# MPU_9250.net
KiCad netlist of a schematic drawn in Altium Designer
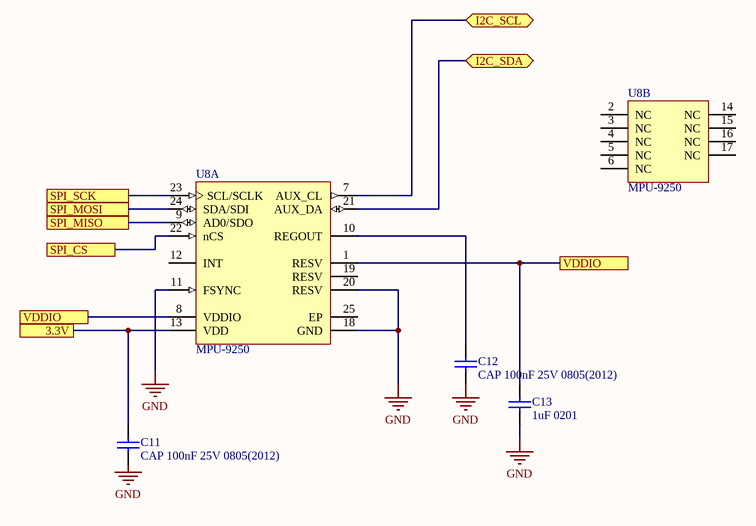
[diagram p0: MPU 9250.SchDoc]

(export (version "E")
  (design (tool "Eeschema 10.0.6"))
  (components
    (comp (ref "C11")
      (value "CAP 100nF 25V 0805(2012)")
      (footprint "CAPC0805(2012)145_M")
      (fields (field (name "TOLERANCE") "Â±5%"))
      (libsource (lib "Altium Content Vault") (part "CAP"))
    )
    (comp (ref "C12")
      (value "CAP 100nF 25V 0805(2012)")
      (footprint "CAPC0805(2012)145_M")
      (fields (field (name "TOLERANCE") "Â±5%"))
      (libsource (lib "Altium Content Vault") (part "CAP"))
    )
    (comp (ref "C13")
      (value "1uF 0201")
      (footprint "CAPC0603X33X15LL03T05")
      (description "GRM033R60J105ME11D")
      (fields (field (name "VOLTAGE") "6.3V"))
      (libsource (lib "CAP 0201") (part "CMP-2010-00405-1"))
    )
    (comp (ref "U8")
      (value "MPU-9250")
      (footprint "INSE-QFN-24-1700X1540TP_L")
      (description "9-axis MotionTracking device, 2.4 to 3,6 V, -40 to 85 degC, 24-Pin QFN, RoHS, Tape and Reel")
      (fields (field (name "MANUFACTURER") "InvenSense"))
      (libsource (lib "MPU-9250") (part "CMP-2100-03657-1"))
    )
  )
  (nets
    (net (code "1") (name "/3.3V") (class "Default")
      (node (ref "C11") (pin "2") (pinfunction "2_2") (pintype "passive"))
      (node (ref "U8") (pin "13") (pinfunction "VDD_13") (pintype "power_in"))
    )
    (net (code "2") (name "/I2C_SCL") (class "Default")
      (node (ref "U8") (pin "7") (pinfunction "AUX_CL_7") (pintype "output"))
    )
    (net (code "3") (name "/I2C_SDA") (class "Default")
      (node (ref "U8") (pin "21") (pinfunction "AUX_DA_21") (pintype "bidirectional"))
    )
    (net (code "4") (name "/SPI_CS") (class "Default")
      (node (ref "U8") (pin "22") (pinfunction "nCS_22") (pintype "input"))
    )
    (net (code "5") (name "/SPI_MISO") (class "Default")
      (node (ref "U8") (pin "9") (pinfunction "AD0/SDO_9") (pintype "bidirectional"))
    )
    (net (code "6") (name "/SPI_MOSI") (class "Default")
      (node (ref "U8") (pin "24") (pinfunction "SDA/SDI_24") (pintype "bidirectional"))
    )
    (net (code "7") (name "/SPI_SCK") (class "Default")
      (node (ref "U8") (pin "23") (pinfunction "SCL/SCLK_23") (pintype "input"))
    )
    (net (code "8") (name "/VDDIO") (class "Default")
      (node (ref "C13") (pin "2") (pinfunction "2_2") (pintype "passive"))
      (node (ref "U8") (pin "1") (pinfunction "RESV_1") (pintype "power_in"))
      (node (ref "U8") (pin "8") (pinfunction "VDDIO_8") (pintype "power_in"))
    )
    (net (code "9") (name "GND") (class "Default")
      (node (ref "C12") (pin "1") (pinfunction "1_1") (pintype "passive"))
      (node (ref "C13") (pin "1") (pinfunction "1_1") (pintype "passive"))
      (node (ref "U8") (pin "11") (pinfunction "FSYNC_11") (pintype "input"))
      (node (ref "U8") (pin "18") (pinfunction "GND_18") (pintype "power_in"))
      (node (ref "U8") (pin "20") (pinfunction "RESV_20") (pintype "power_in"))
    )
    (net (code "10") (name "Net-(U8A-REGOUT)") (class "Default")
      (node (ref "C12") (pin "2") (pinfunction "2_2") (pintype "passive"))
      (node (ref "U8") (pin "10") (pinfunction "REGOUT_10") (pintype "passive"))
    )
    (net (code "11") (name "unconnected-(C11-Pad1)") (class "Default")
      (node (ref "C11") (pin "1") (pinfunction "1_1") (pintype "passive"))
    )
    (net (code "12") (name "unconnected-(U8A-EP-Pad25)") (class "Default")
      (node (ref "U8") (pin "25") (pinfunction "EP_25") (pintype "passive"))
    )
    (net (code "13") (name "unconnected-(U8A-INT-Pad12)") (class "Default")
      (node (ref "U8") (pin "12") (pinfunction "INT_12") (pintype "tri_state"))
    )
    (net (code "14") (name "unconnected-(U8A-RESV-Pad19)") (class "Default")
      (node (ref "U8") (pin "19") (pinfunction "RESV_19") (pintype "passive"))
    )
    (net (code "15") (name "unconnected-(U8B-NC-Pad2)") (class "Default")
      (node (ref "U8") (pin "2") (pinfunction "NC_2") (pintype "passive"))
    )
    (net (code "16") (name "unconnected-(U8B-NC-Pad3)") (class "Default")
      (node (ref "U8") (pin "3") (pinfunction "NC_3") (pintype "passive"))
    )
    (net (code "17") (name "unconnected-(U8B-NC-Pad4)") (class "Default")
      (node (ref "U8") (pin "4") (pinfunction "NC_4") (pintype "passive"))
    )
    (net (code "18") (name "unconnected-(U8B-NC-Pad5)") (class "Default")
      (node (ref "U8") (pin "5") (pinfunction "NC_5") (pintype "passive"))
    )
    (net (code "19") (name "unconnected-(U8B-NC-Pad6)") (class "Default")
      (node (ref "U8") (pin "6") (pinfunction "NC_6") (pintype "passive"))
    )
    (net (code "20") (name "unconnected-(U8B-NC-Pad14)") (class "Default")
      (node (ref "U8") (pin "14") (pinfunction "NC_14") (pintype "passive"))
    )
    (net (code "21") (name "unconnected-(U8B-NC-Pad15)") (class "Default")
      (node (ref "U8") (pin "15") (pinfunction "NC_15") (pintype "passive"))
    )
    (net (code "22") (name "unconnected-(U8B-NC-Pad16)") (class "Default")
      (node (ref "U8") (pin "16") (pinfunction "NC_16") (pintype "passive"))
    )
    (net (code "23") (name "unconnected-(U8B-NC-Pad17)") (class "Default")
      (node (ref "U8") (pin "17") (pinfunction "NC_17") (pintype "passive"))
    )
  )
)
